# power_supply.net
KiCad netlist of a schematic drawn in Altium Designer
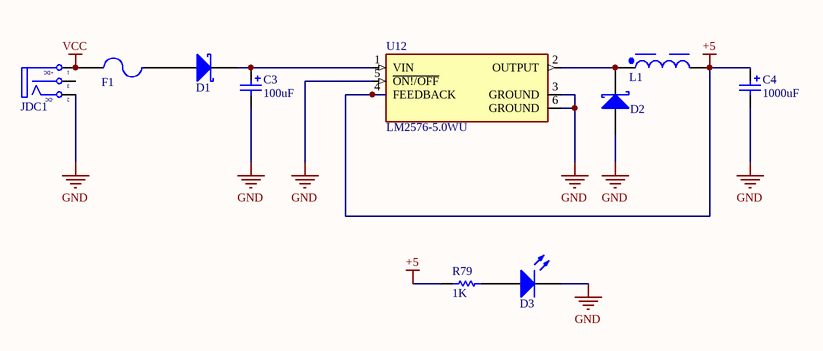
[diagram p0: power_supply.SchDoc]

(export (version "E")
  (design (tool "Eeschema 10.0.6"))
  (components
    (comp (ref "C3")
      (value "100uF")
      (footprint "WCAP-ATG8_D8H11.5")
      (description "WCAP-ATG8 Aluminum Electrolytic Capacitor, Radial THT, D8xH11.5mm, 100uF, 50V")
      (fields
        (field (name "MANUFACTURER") "Wurth Elektronik")
        (field (name "MANUFACTURER PART NUMBER") "860010674014")
      )
      (libsource (lib "Altium_WCAP-ATG8 (rev22a)") (part "860010674014"))
    )
    (comp (ref "C4")
      (value "1000uF")
      (footprint "WCAP-ATG8_D8H16")
      (description "WCAP-ATG8 Aluminum Electrolytic Capacitor, Radial THT, D8xH16mm, 1000uF, 10V")
      (fields
        (field (name "MANUFACTURER") "Wurth Elektronik")
        (field (name "MANUFACTURER PART NUMBER") "860010274015")
      )
      (libsource (lib "Altium_WCAP-ATG8 (rev22a)") (part "860010274015"))
    )
    (comp (ref "D1")
      (value "D Schottky")
      (footprint "SS34")
      (description "Schottky Diode")
      (fields (field (name "PUBLISHER") "Altium Limited"))
      (libsource (lib "PIF_Library") (part "D Schottky"))
    )
    (comp (ref "D2")
      (value "D Schottky")
      (footprint "SS34")
      (description "Schottky Diode")
      (fields (field (name "PUBLISHER") "Altium Limited"))
      (libsource (lib "PIF_Library") (part "D Schottky"))
    )
    (comp (ref "D3")
      (value "LED SMD")
      (footprint "LED_0603_Blue")
      (description "LED")
      (libsource (lib "PIF_Library") (part "LED SMD"))
    )
    (comp (ref "F1") (value "Fuse") (footprint "FUSE SMD") (libsource (lib "PIF_Library") (part "Fuse")))
    (comp (ref "JDC1")
      (value "Jack DC")
      (footprint "DC-IN")
      (description "Jack DC input")
      (libsource (lib "PIF_Library") (part "Jack DC"))
    )
    (comp (ref "L1")
      (value "100µH, 0.57A")
      (footprint "WE-PD2_5848")
      (description "WE-PD2 SMT Power Inductor, 5848, 100µH, 0.57A, 0.65Ω")
      (fields
        (field (name "MANUFACTURER PART NUMBER") "74477420")
        (field (name "MANUFACTURER") "Wurth Elektronik")
      )
      (libsource (lib "WE-PD2 (rev22b)") (part "74477420"))
    )
    (comp (ref "R79")
      (value "1K")
      (footprint "RES-SM-0603")
      (description "Resistor")
      (fields (field (name "Comment") "RESISTOR SMD"))
      (libsource (lib "PIF_Library") (part "RESISTOR SMD"))
    )
    (comp (ref "U12")
      (value "LM2576-5.0WU")
      (footprint "DPAK6P170_1524X459L254X81N")
      (fields (field (name "MF") "Microchip"))
      (libsource (lib "LM2576-5.0WU") (part "LM2576-5.0WU"))
    )
  )
  (nets
    (net (code "1") (name "+5") (class "Default")
      (node (ref "C4") (pin "1") (pinfunction "P_1") (pintype "passive"))
      (node (ref "L1") (pin "2") (pinfunction "2_2") (pintype "passive"))
      (node (ref "R79") (pin "1") (pinfunction "1_1") (pintype "passive"))
      (node (ref "U12") (pin "4") (pinfunction "FEEDBACK_4") (pintype "bidirectional"))
    )
    (net (code "2") (name "GND") (class "Default")
      (node (ref "C3") (pin "2") (pinfunction "N_2") (pintype "passive"))
      (node (ref "C4") (pin "2") (pinfunction "N_2") (pintype "passive"))
      (node (ref "D2") (pin "1") (pinfunction "A_1") (pintype "passive"))
      (node (ref "D3") (pin "2") (pinfunction "K_2") (pintype "passive"))
      (node (ref "JDC1") (pin "2") (pinfunction "TN_2") (pintype "passive"))
      (node (ref "U12") (pin "3") (pinfunction "GROUND_3") (pintype "power_in"))
      (node (ref "U12") (pin "5") (pinfunction "~{ON!/OFF}_5") (pintype "input"))
      (node (ref "U12") (pin "6") (pinfunction "GROUND_6") (pintype "power_in"))
    )
    (net (code "3") (name "Net-(C3-P)") (class "Default")
      (node (ref "C3") (pin "1") (pinfunction "P_1") (pintype "passive"))
      (node (ref "D1") (pin "2") (pinfunction "K_2") (pintype "passive"))
      (node (ref "U12") (pin "1") (pinfunction "VIN_1") (pintype "input"))
    )
    (net (code "4") (name "Net-(D1-A)") (class "Default")
      (node (ref "D1") (pin "1") (pinfunction "A_1") (pintype "passive"))
      (node (ref "F1") (pin "2") (pinfunction "2_2") (pintype "passive"))
    )
    (net (code "5") (name "Net-(D2-K)") (class "Default")
      (node (ref "D2") (pin "2") (pinfunction "K_2") (pintype "passive"))
      (node (ref "L1") (pin "1") (pinfunction "1_1") (pintype "passive"))
      (node (ref "U12") (pin "2") (pinfunction "OUTPUT_2") (pintype "output"))
    )
    (net (code "6") (name "Net-(D3-A)") (class "Default")
      (node (ref "D3") (pin "1") (pinfunction "A_1") (pintype "passive"))
      (node (ref "R79") (pin "2") (pinfunction "2_2") (pintype "passive"))
    )
    (net (code "7") (name "VCC") (class "Default")
      (node (ref "F1") (pin "1") (pinfunction "1_1") (pintype "passive"))
      (node (ref "JDC1") (pin "1") (pinfunction "T_1") (pintype "passive"))
    )
    (net (code "8") (name "unconnected-(JDC1-S-Pad3)") (class "Default")
      (node (ref "JDC1") (pin "3") (pinfunction "S_3") (pintype "power_in"))
    )
  )
)
